# SprinklerController.net
KiCad netlist of a schematic drawn in EAGLE
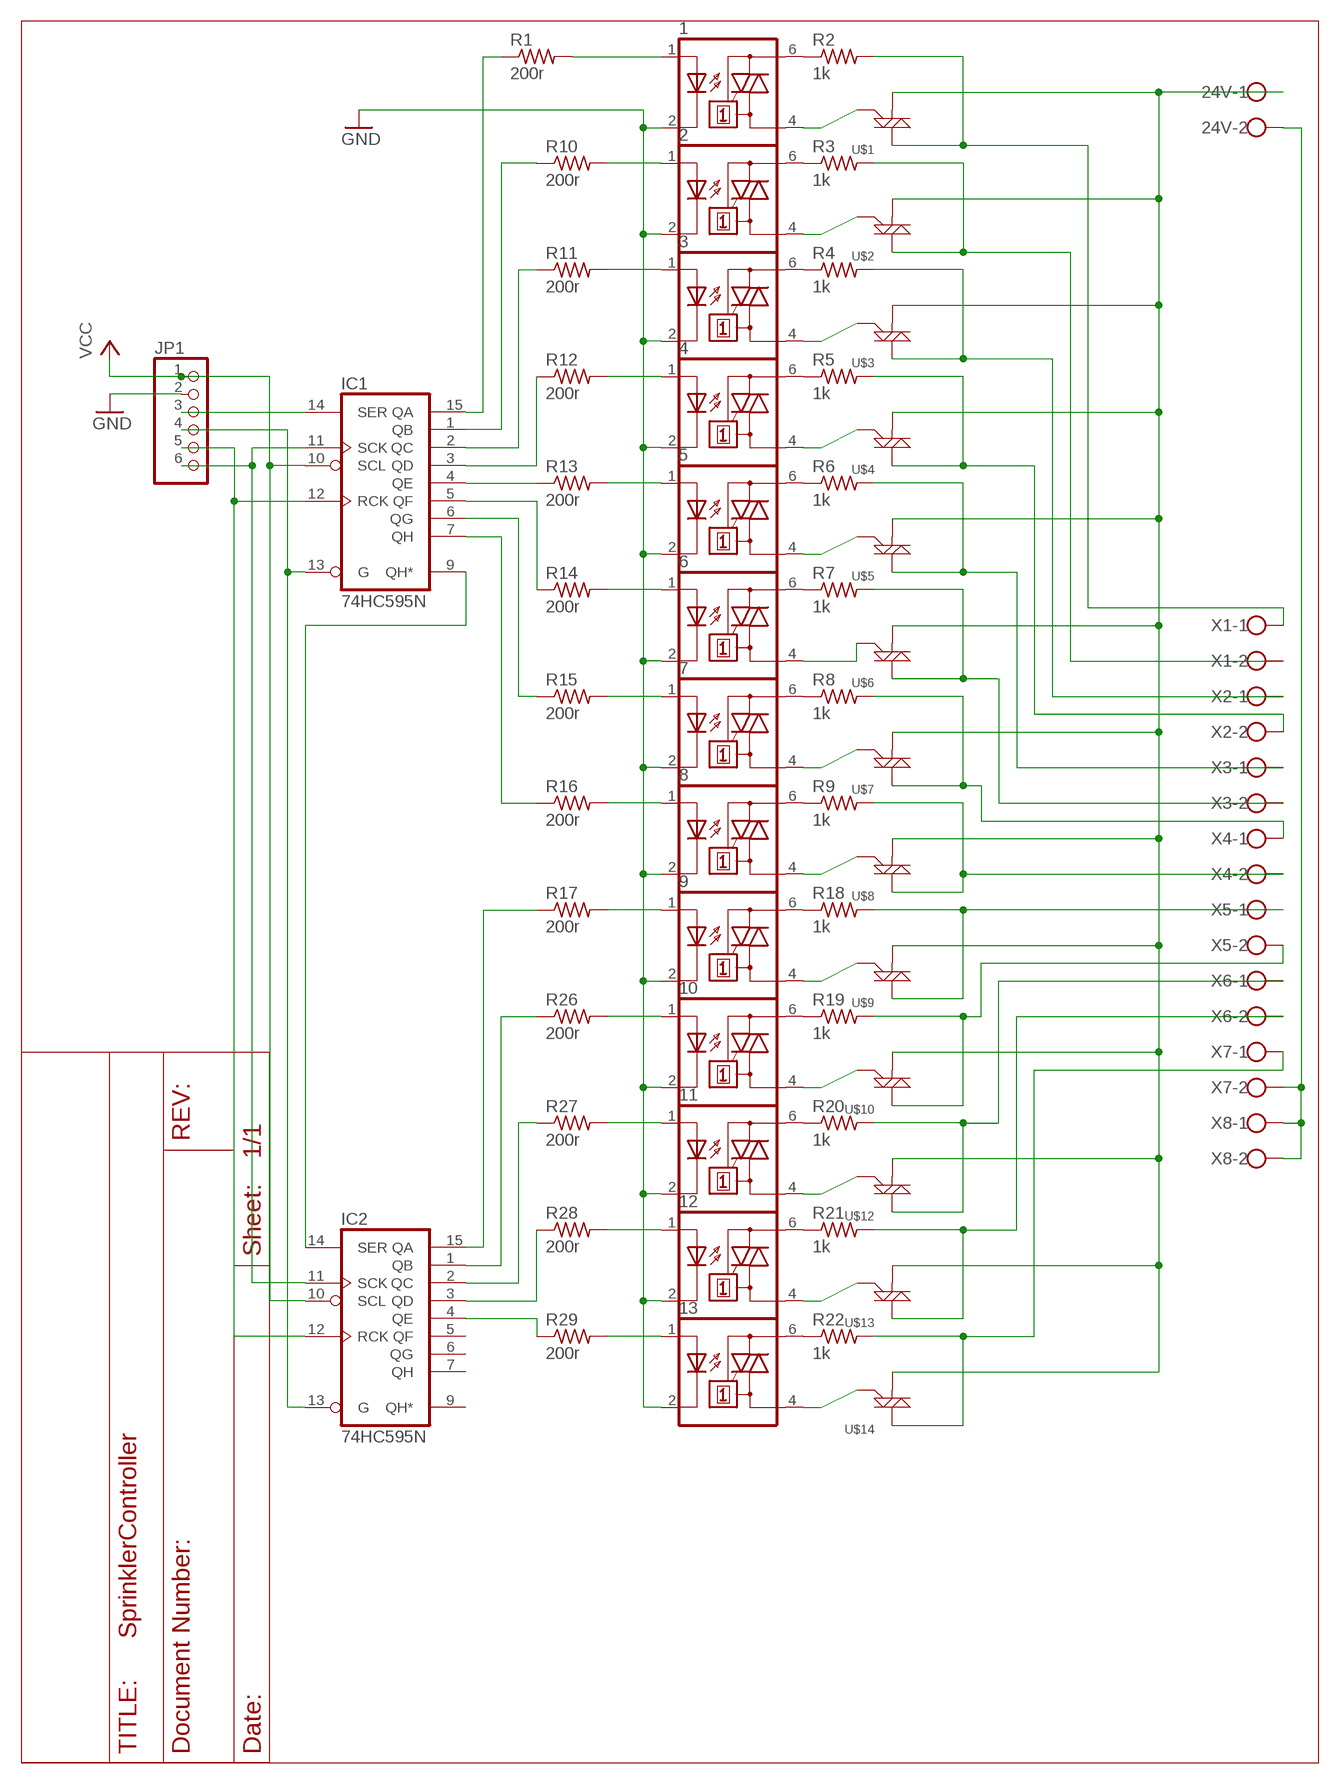
[diagram p0: schematic, sheet 1]

(export (version "E")
  (design (tool "Eeschema 10.0.6"))
  (components
    (comp (ref "1")
      (value "MOC3021M")
      (footprint "eagle-import:DIL06")
      (fields (field (name "MF") "FAIRCHILD SEMICONDUCTOR") (field (name "MPN") "MOC3021-M"))
      (libsource (lib "eagle-import") (part "MOC30M21"))
    )
    (comp (ref "2")
      (value "MOC3021M")
      (footprint "eagle-import:DIL06")
      (fields (field (name "MF") "FAIRCHILD SEMICONDUCTOR") (field (name "MPN") "MOC3021-M"))
      (libsource (lib "eagle-import") (part "MOC30M21"))
    )
    (comp (ref "3")
      (value "MOC3021M")
      (footprint "eagle-import:DIL06")
      (fields (field (name "MF") "FAIRCHILD SEMICONDUCTOR") (field (name "MPN") "MOC3021-M"))
      (libsource (lib "eagle-import") (part "MOC30M21"))
    )
    (comp (ref "4")
      (value "MOC3021M")
      (footprint "eagle-import:DIL06")
      (fields (field (name "MF") "FAIRCHILD SEMICONDUCTOR") (field (name "MPN") "MOC3021-M"))
      (libsource (lib "eagle-import") (part "MOC30M21"))
    )
    (comp (ref "5")
      (value "MOC3021M")
      (footprint "eagle-import:DIL06")
      (fields (field (name "MF") "FAIRCHILD SEMICONDUCTOR") (field (name "MPN") "MOC3021-M"))
      (libsource (lib "eagle-import") (part "MOC30M21"))
    )
    (comp (ref "6")
      (value "MOC3021M")
      (footprint "eagle-import:DIL06")
      (fields (field (name "MF") "FAIRCHILD SEMICONDUCTOR") (field (name "MPN") "MOC3021-M"))
      (libsource (lib "eagle-import") (part "MOC30M21"))
    )
    (comp (ref "7")
      (value "MOC3021M")
      (footprint "eagle-import:DIL06")
      (fields (field (name "MF") "FAIRCHILD SEMICONDUCTOR") (field (name "MPN") "MOC3021-M"))
      (libsource (lib "eagle-import") (part "MOC30M21"))
    )
    (comp (ref "8")
      (value "MOC3021M")
      (footprint "eagle-import:DIL06")
      (fields (field (name "MF") "FAIRCHILD SEMICONDUCTOR") (field (name "MPN") "MOC3021-M"))
      (libsource (lib "eagle-import") (part "MOC30M21"))
    )
    (comp (ref "9")
      (value "MOC3021M")
      (footprint "eagle-import:DIL06")
      (fields (field (name "MF") "FAIRCHILD SEMICONDUCTOR") (field (name "MPN") "MOC3021-M"))
      (libsource (lib "eagle-import") (part "MOC30M21"))
    )
    (comp (ref "10")
      (value "MOC3021M")
      (footprint "eagle-import:DIL06")
      (fields (field (name "MF") "FAIRCHILD SEMICONDUCTOR") (field (name "MPN") "MOC3021-M"))
      (libsource (lib "eagle-import") (part "MOC30M21"))
    )
    (comp (ref "11")
      (value "MOC3021M")
      (footprint "eagle-import:DIL06")
      (fields (field (name "MF") "FAIRCHILD SEMICONDUCTOR") (field (name "MPN") "MOC3021-M"))
      (libsource (lib "eagle-import") (part "MOC30M21"))
    )
    (comp (ref "12")
      (value "MOC3021M")
      (footprint "eagle-import:DIL06")
      (fields (field (name "MF") "FAIRCHILD SEMICONDUCTOR") (field (name "MPN") "MOC3021-M"))
      (libsource (lib "eagle-import") (part "MOC30M21"))
    )
    (comp (ref "13")
      (value "MOC3021M")
      (footprint "eagle-import:DIL06")
      (fields (field (name "MF") "FAIRCHILD SEMICONDUCTOR") (field (name "MPN") "MOC3021-M"))
      (libsource (lib "eagle-import") (part "MOC30M21"))
    )
    (comp (ref "24V")
      (value "W237-102")
      (footprint "eagle-import:W237-102")
      (fields (field (name "MPN") "237-102"))
      (libsource (lib "eagle-import") (part "W237-102"))
    )
    (comp (ref "IC1")
      (value "74HC595N")
      (footprint "eagle-import:DIL16")
      (libsource (lib "eagle-import") (part "74595NLS"))
    )
    (comp (ref "IC2")
      (value "74HC595N")
      (footprint "eagle-import:DIL16")
      (libsource (lib "eagle-import") (part "74595NLS"))
    )
    (comp (ref "JP1")
      (value "PINHD-1X6")
      (footprint "eagle-import:1X06")
      (libsource (lib "eagle-import") (part "PINHD-1X6"))
    )
    (comp (ref "R1")
      (value "200r")
      (footprint "eagle-import:0204_7")
      (libsource (lib "eagle-import") (part "R-US_0204/7"))
    )
    (comp (ref "R2")
      (value "1k")
      (footprint "eagle-import:0204_7")
      (libsource (lib "eagle-import") (part "R-US_0204/7"))
    )
    (comp (ref "R3")
      (value "1k")
      (footprint "eagle-import:0204_7")
      (libsource (lib "eagle-import") (part "R-US_0204/7"))
    )
    (comp (ref "R4")
      (value "1k")
      (footprint "eagle-import:0204_7")
      (libsource (lib "eagle-import") (part "R-US_0204/7"))
    )
    (comp (ref "R5")
      (value "1k")
      (footprint "eagle-import:0204_7")
      (libsource (lib "eagle-import") (part "R-US_0204/7"))
    )
    (comp (ref "R6")
      (value "1k")
      (footprint "eagle-import:0204_7")
      (libsource (lib "eagle-import") (part "R-US_0204/7"))
    )
    (comp (ref "R7")
      (value "1k")
      (footprint "eagle-import:0204_7")
      (libsource (lib "eagle-import") (part "R-US_0204/7"))
    )
    (comp (ref "R8")
      (value "1k")
      (footprint "eagle-import:0204_7")
      (libsource (lib "eagle-import") (part "R-US_0204/7"))
    )
    (comp (ref "R9")
      (value "1k")
      (footprint "eagle-import:0204_7")
      (libsource (lib "eagle-import") (part "R-US_0204/7"))
    )
    (comp (ref "R10")
      (value "200r")
      (footprint "eagle-import:0204_7")
      (libsource (lib "eagle-import") (part "R-US_0204/7"))
    )
    (comp (ref "R11")
      (value "200r")
      (footprint "eagle-import:0204_7")
      (libsource (lib "eagle-import") (part "R-US_0204/7"))
    )
    (comp (ref "R12")
      (value "200r")
      (footprint "eagle-import:0204_7")
      (libsource (lib "eagle-import") (part "R-US_0204/7"))
    )
    (comp (ref "R13")
      (value "200r")
      (footprint "eagle-import:0204_7")
      (libsource (lib "eagle-import") (part "R-US_0204/7"))
    )
    (comp (ref "R14")
      (value "200r")
      (footprint "eagle-import:0204_7")
      (libsource (lib "eagle-import") (part "R-US_0204/7"))
    )
    (comp (ref "R15")
      (value "200r")
      (footprint "eagle-import:0204_7")
      (libsource (lib "eagle-import") (part "R-US_0204/7"))
    )
    (comp (ref "R16")
      (value "200r")
      (footprint "eagle-import:0204_7")
      (libsource (lib "eagle-import") (part "R-US_0204/7"))
    )
    (comp (ref "R17")
      (value "200r")
      (footprint "eagle-import:0204_7")
      (libsource (lib "eagle-import") (part "R-US_0204/7"))
    )
    (comp (ref "R18")
      (value "1k")
      (footprint "eagle-import:0204_7")
      (libsource (lib "eagle-import") (part "R-US_0204/7"))
    )
    (comp (ref "R19")
      (value "1k")
      (footprint "eagle-import:0204_7")
      (libsource (lib "eagle-import") (part "R-US_0204/7"))
    )
    (comp (ref "R20")
      (value "1k")
      (footprint "eagle-import:0204_7")
      (libsource (lib "eagle-import") (part "R-US_0204/7"))
    )
    (comp (ref "R21")
      (value "1k")
      (footprint "eagle-import:0204_7")
      (libsource (lib "eagle-import") (part "R-US_0204/7"))
    )
    (comp (ref "R22")
      (value "1k")
      (footprint "eagle-import:0204_7")
      (libsource (lib "eagle-import") (part "R-US_0204/7"))
    )
    (comp (ref "R26")
      (value "200r")
      (footprint "eagle-import:0204_7")
      (libsource (lib "eagle-import") (part "R-US_0204/7"))
    )
    (comp (ref "R27")
      (value "200r")
      (footprint "eagle-import:0204_7")
      (libsource (lib "eagle-import") (part "R-US_0204/7"))
    )
    (comp (ref "R28")
      (value "200r")
      (footprint "eagle-import:0204_7")
      (libsource (lib "eagle-import") (part "R-US_0204/7"))
    )
    (comp (ref "R29")
      (value "200r")
      (footprint "eagle-import:0204_7")
      (libsource (lib "eagle-import") (part "R-US_0204/7"))
    )
    (comp (ref "U$1")
      (value "TRIACPTH")
      (footprint "eagle-import:TO-92")
      (libsource (lib "eagle-import") (part "TRIACPTH"))
    )
    (comp (ref "U$2")
      (value "TRIACPTH")
      (footprint "eagle-import:TO-92")
      (libsource (lib "eagle-import") (part "TRIACPTH"))
    )
    (comp (ref "U$3")
      (value "TRIACPTH")
      (footprint "eagle-import:TO-92")
      (libsource (lib "eagle-import") (part "TRIACPTH"))
    )
    (comp (ref "U$4")
      (value "TRIACPTH")
      (footprint "eagle-import:TO-92")
      (libsource (lib "eagle-import") (part "TRIACPTH"))
    )
    (comp (ref "U$5")
      (value "TRIACPTH")
      (footprint "eagle-import:TO-92")
      (libsource (lib "eagle-import") (part "TRIACPTH"))
    )
    (comp (ref "U$6")
      (value "TRIACPTH")
      (footprint "eagle-import:TO-92")
      (libsource (lib "eagle-import") (part "TRIACPTH"))
    )
    (comp (ref "U$7")
      (value "TRIACPTH")
      (footprint "eagle-import:TO-92")
      (libsource (lib "eagle-import") (part "TRIACPTH"))
    )
    (comp (ref "U$8")
      (value "TRIACPTH")
      (footprint "eagle-import:TO-92")
      (libsource (lib "eagle-import") (part "TRIACPTH"))
    )
    (comp (ref "U$9")
      (value "TRIACPTH")
      (footprint "eagle-import:TO-92")
      (libsource (lib "eagle-import") (part "TRIACPTH"))
    )
    (comp (ref "U$10")
      (value "TRIACPTH")
      (footprint "eagle-import:TO-92")
      (libsource (lib "eagle-import") (part "TRIACPTH"))
    )
    (comp (ref "U$12")
      (value "TRIACPTH")
      (footprint "eagle-import:TO-92")
      (libsource (lib "eagle-import") (part "TRIACPTH"))
    )
    (comp (ref "U$13")
      (value "TRIACPTH")
      (footprint "eagle-import:TO-92")
      (libsource (lib "eagle-import") (part "TRIACPTH"))
    )
    (comp (ref "U$14")
      (value "TRIACPTH")
      (footprint "eagle-import:TO-92")
      (libsource (lib "eagle-import") (part "TRIACPTH"))
    )
    (comp (ref "X1")
      (value "W237-102")
      (footprint "eagle-import:W237-102")
      (fields (field (name "MPN") "237-102"))
      (libsource (lib "eagle-import") (part "W237-102"))
    )
    (comp (ref "X2")
      (value "W237-102")
      (footprint "eagle-import:W237-102")
      (fields (field (name "MPN") "237-102"))
      (libsource (lib "eagle-import") (part "W237-102"))
    )
    (comp (ref "X3")
      (value "W237-102")
      (footprint "eagle-import:W237-102")
      (fields (field (name "MPN") "237-102"))
      (libsource (lib "eagle-import") (part "W237-102"))
    )
    (comp (ref "X4")
      (value "W237-102")
      (footprint "eagle-import:W237-102")
      (fields (field (name "MPN") "237-102"))
      (libsource (lib "eagle-import") (part "W237-102"))
    )
    (comp (ref "X5")
      (value "W237-102")
      (footprint "eagle-import:W237-102")
      (fields (field (name "MPN") "237-102"))
      (libsource (lib "eagle-import") (part "W237-102"))
    )
    (comp (ref "X6")
      (value "W237-102")
      (footprint "eagle-import:W237-102")
      (fields (field (name "MPN") "237-102"))
      (libsource (lib "eagle-import") (part "W237-102"))
    )
    (comp (ref "X7")
      (value "W237-102")
      (footprint "eagle-import:W237-102")
      (fields (field (name "MPN") "237-102"))
      (libsource (lib "eagle-import") (part "W237-102"))
    )
    (comp (ref "X8")
      (value "W237-102")
      (footprint "eagle-import:W237-102")
      (fields (field (name "MPN") "237-102"))
      (libsource (lib "eagle-import") (part "W237-102"))
    )
  )
  (nets
    (net (code "1") (name "GND") (class "Default")
      (node (ref "1") (pin "2") (pinfunction "C_2") (pintype "passive"))
      (node (ref "10") (pin "2") (pinfunction "C_2") (pintype "passive"))
      (node (ref "11") (pin "2") (pinfunction "C_2") (pintype "passive"))
      (node (ref "12") (pin "2") (pinfunction "C_2") (pintype "passive"))
      (node (ref "13") (pin "2") (pinfunction "C_2") (pintype "passive"))
      (node (ref "2") (pin "2") (pinfunction "C_2") (pintype "passive"))
      (node (ref "3") (pin "2") (pinfunction "C_2") (pintype "passive"))
      (node (ref "4") (pin "2") (pinfunction "C_2") (pintype "passive"))
      (node (ref "5") (pin "2") (pinfunction "C_2") (pintype "passive"))
      (node (ref "6") (pin "2") (pinfunction "C_2") (pintype "passive"))
      (node (ref "7") (pin "2") (pinfunction "C_2") (pintype "passive"))
      (node (ref "8") (pin "2") (pinfunction "C_2") (pintype "passive"))
      (node (ref "9") (pin "2") (pinfunction "C_2") (pintype "passive"))
      (node (ref "JP1") (pin "2") (pinfunction "2_2") (pintype "passive"))
    )
    (net (code "2") (name "Net-(1-A)") (class "Default")
      (node (ref "1") (pin "1") (pinfunction "A_1") (pintype "passive"))
      (node (ref "R1") (pin "2") (pinfunction "2_2") (pintype "passive"))
    )
    (net (code "3") (name "Net-(1-A1)") (class "Default")
      (node (ref "1") (pin "4") (pinfunction "A1_4") (pintype "passive"))
      (node (ref "U$1") (pin "2") (pinfunction "G_2") (pintype "bidirectional"))
    )
    (net (code "4") (name "Net-(1-A2)") (class "Default")
      (node (ref "1") (pin "6") (pinfunction "A2_6") (pintype "passive"))
      (node (ref "R2") (pin "1") (pinfunction "1_1") (pintype "passive"))
    )
    (net (code "5") (name "Net-(2-A)") (class "Default")
      (node (ref "2") (pin "1") (pinfunction "A_1") (pintype "passive"))
      (node (ref "R10") (pin "2") (pinfunction "2_2") (pintype "passive"))
    )
    (net (code "6") (name "Net-(2-A1)") (class "Default")
      (node (ref "2") (pin "4") (pinfunction "A1_4") (pintype "passive"))
      (node (ref "U$2") (pin "2") (pinfunction "G_2") (pintype "bidirectional"))
    )
    (net (code "7") (name "Net-(2-A2)") (class "Default")
      (node (ref "2") (pin "6") (pinfunction "A2_6") (pintype "passive"))
      (node (ref "R3") (pin "1") (pinfunction "1_1") (pintype "passive"))
    )
    (net (code "8") (name "Net-(3-A)") (class "Default")
      (node (ref "3") (pin "1") (pinfunction "A_1") (pintype "passive"))
      (node (ref "R11") (pin "2") (pinfunction "2_2") (pintype "passive"))
    )
    (net (code "9") (name "Net-(3-A1)") (class "Default")
      (node (ref "3") (pin "4") (pinfunction "A1_4") (pintype "passive"))
      (node (ref "U$3") (pin "2") (pinfunction "G_2") (pintype "bidirectional"))
    )
    (net (code "10") (name "Net-(3-A2)") (class "Default")
      (node (ref "3") (pin "6") (pinfunction "A2_6") (pintype "passive"))
      (node (ref "R4") (pin "1") (pinfunction "1_1") (pintype "passive"))
    )
    (net (code "11") (name "Net-(4-A)") (class "Default")
      (node (ref "4") (pin "1") (pinfunction "A_1") (pintype "passive"))
      (node (ref "R12") (pin "2") (pinfunction "2_2") (pintype "passive"))
    )
    (net (code "12") (name "Net-(4-A1)") (class "Default")
      (node (ref "4") (pin "4") (pinfunction "A1_4") (pintype "passive"))
      (node (ref "U$4") (pin "2") (pinfunction "G_2") (pintype "bidirectional"))
    )
    (net (code "13") (name "Net-(4-A2)") (class "Default")
      (node (ref "4") (pin "6") (pinfunction "A2_6") (pintype "passive"))
      (node (ref "R5") (pin "1") (pinfunction "1_1") (pintype "passive"))
    )
    (net (code "14") (name "Net-(5-A)") (class "Default")
      (node (ref "5") (pin "1") (pinfunction "A_1") (pintype "passive"))
      (node (ref "R13") (pin "2") (pinfunction "2_2") (pintype "passive"))
    )
    (net (code "15") (name "Net-(5-A1)") (class "Default")
      (node (ref "5") (pin "4") (pinfunction "A1_4") (pintype "passive"))
      (node (ref "U$5") (pin "2") (pinfunction "G_2") (pintype "bidirectional"))
    )
    (net (code "16") (name "Net-(5-A2)") (class "Default")
      (node (ref "5") (pin "6") (pinfunction "A2_6") (pintype "passive"))
      (node (ref "R6") (pin "1") (pinfunction "1_1") (pintype "passive"))
    )
    (net (code "17") (name "Net-(6-A)") (class "Default")
      (node (ref "6") (pin "1") (pinfunction "A_1") (pintype "passive"))
      (node (ref "R14") (pin "2") (pinfunction "2_2") (pintype "passive"))
    )
    (net (code "18") (name "Net-(6-A1)") (class "Default")
      (node (ref "6") (pin "4") (pinfunction "A1_4") (pintype "passive"))
      (node (ref "U$6") (pin "2") (pinfunction "G_2") (pintype "bidirectional"))
    )
    (net (code "19") (name "Net-(6-A2)") (class "Default")
      (node (ref "6") (pin "6") (pinfunction "A2_6") (pintype "passive"))
      (node (ref "R7") (pin "1") (pinfunction "1_1") (pintype "passive"))
    )
    (net (code "20") (name "Net-(7-A)") (class "Default")
      (node (ref "7") (pin "1") (pinfunction "A_1") (pintype "passive"))
      (node (ref "R15") (pin "2") (pinfunction "2_2") (pintype "passive"))
    )
    (net (code "21") (name "Net-(7-A1)") (class "Default")
      (node (ref "7") (pin "4") (pinfunction "A1_4") (pintype "passive"))
      (node (ref "U$7") (pin "2") (pinfunction "G_2") (pintype "bidirectional"))
    )
    (net (code "22") (name "Net-(7-A2)") (class "Default")
      (node (ref "7") (pin "6") (pinfunction "A2_6") (pintype "passive"))
      (node (ref "R8") (pin "1") (pinfunction "1_1") (pintype "passive"))
    )
    (net (code "23") (name "Net-(8-A)") (class "Default")
      (node (ref "8") (pin "1") (pinfunction "A_1") (pintype "passive"))
      (node (ref "R16") (pin "2") (pinfunction "2_2") (pintype "passive"))
    )
    (net (code "24") (name "Net-(8-A1)") (class "Default")
      (node (ref "8") (pin "4") (pinfunction "A1_4") (pintype "passive"))
      (node (ref "U$8") (pin "2") (pinfunction "G_2") (pintype "bidirectional"))
    )
    (net (code "25") (name "Net-(8-A2)") (class "Default")
      (node (ref "8") (pin "6") (pinfunction "A2_6") (pintype "passive"))
      (node (ref "R9") (pin "1") (pinfunction "1_1") (pintype "passive"))
    )
    (net (code "26") (name "Net-(9-A)") (class "Default")
      (node (ref "9") (pin "1") (pinfunction "A_1") (pintype "passive"))
      (node (ref "R17") (pin "2") (pinfunction "2_2") (pintype "passive"))
    )
    (net (code "27") (name "Net-(9-A1)") (class "Default")
      (node (ref "9") (pin "4") (pinfunction "A1_4") (pintype "passive"))
      (node (ref "U$9") (pin "2") (pinfunction "G_2") (pintype "bidirectional"))
    )
    (net (code "28") (name "Net-(9-A2)") (class "Default")
      (node (ref "9") (pin "6") (pinfunction "A2_6") (pintype "passive"))
      (node (ref "R18") (pin "1") (pinfunction "1_1") (pintype "passive"))
    )
    (net (code "29") (name "Net-(10-A)") (class "Default")
      (node (ref "10") (pin "1") (pinfunction "A_1") (pintype "passive"))
      (node (ref "R26") (pin "2") (pinfunction "2_2") (pintype "passive"))
    )
    (net (code "30") (name "Net-(10-A1)") (class "Default")
      (node (ref "10") (pin "4") (pinfunction "A1_4") (pintype "passive"))
      (node (ref "U$10") (pin "2") (pinfunction "G_2") (pintype "bidirectional"))
    )
    (net (code "31") (name "Net-(10-A2)") (class "Default")
      (node (ref "10") (pin "6") (pinfunction "A2_6") (pintype "passive"))
      (node (ref "R19") (pin "1") (pinfunction "1_1") (pintype "passive"))
    )
    (net (code "32") (name "Net-(11-A)") (class "Default")
      (node (ref "11") (pin "1") (pinfunction "A_1") (pintype "passive"))
      (node (ref "R27") (pin "2") (pinfunction "2_2") (pintype "passive"))
    )
    (net (code "33") (name "Net-(11-A1)") (class "Default")
      (node (ref "11") (pin "4") (pinfunction "A1_4") (pintype "passive"))
      (node (ref "U$12") (pin "2") (pinfunction "G_2") (pintype "bidirectional"))
    )
    (net (code "34") (name "Net-(11-A2)") (class "Default")
      (node (ref "11") (pin "6") (pinfunction "A2_6") (pintype "passive"))
      (node (ref "R20") (pin "1") (pinfunction "1_1") (pintype "passive"))
    )
    (net (code "35") (name "Net-(12-A)") (class "Default")
      (node (ref "12") (pin "1") (pinfunction "A_1") (pintype "passive"))
      (node (ref "R28") (pin "2") (pinfunction "2_2") (pintype "passive"))
    )
    (net (code "36") (name "Net-(12-A1)") (class "Default")
      (node (ref "12") (pin "4") (pinfunction "A1_4") (pintype "passive"))
      (node (ref "U$13") (pin "2") (pinfunction "G_2") (pintype "bidirectional"))
    )
    (net (code "37") (name "Net-(12-A2)") (class "Default")
      (node (ref "12") (pin "6") (pinfunction "A2_6") (pintype "passive"))
      (node (ref "R21") (pin "1") (pinfunction "1_1") (pintype "passive"))
    )
    (net (code "38") (name "Net-(13-A)") (class "Default")
      (node (ref "13") (pin "1") (pinfunction "A_1") (pintype "passive"))
      (node (ref "R29") (pin "2") (pinfunction "2_2") (pintype "passive"))
    )
    (net (code "39") (name "Net-(13-A1)") (class "Default")
      (node (ref "13") (pin "4") (pinfunction "A1_4") (pintype "passive"))
      (node (ref "U$14") (pin "2") (pinfunction "G_2") (pintype "bidirectional"))
    )
    (net (code "40") (name "Net-(13-A2)") (class "Default")
      (node (ref "13") (pin "6") (pinfunction "A2_6") (pintype "passive"))
      (node (ref "R22") (pin "1") (pinfunction "1_1") (pintype "passive"))
    )
    (net (code "41") (name "Net-(24VA-KL)") (class "Default")
      (node (ref "24V") (pin "1") (pinfunction "KL_1") (pintype "passive"))
      (node (ref "U$1") (pin "1") (pinfunction "M1_1") (pintype "bidirectional"))
      (node (ref "U$10") (pin "1") (pinfunction "M1_1") (pintype "bidirectional"))
      (node (ref "U$12") (pin "1") (pinfunction "M1_1") (pintype "bidirectional"))
      (node (ref "U$13") (pin "1") (pinfunction "M1_1") (pintype "bidirectional"))
      (node (ref "U$14") (pin "1") (pinfunction "M1_1") (pintype "bidirectional"))
      (node (ref "U$2") (pin "1") (pinfunction "M1_1") (pintype "bidirectional"))
      (node (ref "U$3") (pin "1") (pinfunction "M1_1") (pintype "bidirectional"))
      (node (ref "U$4") (pin "1") (pinfunction "M1_1") (pintype "bidirectional"))
      (node (ref "U$5") (pin "1") (pinfunction "M1_1") (pintype "bidirectional"))
      (node (ref "U$6") (pin "1") (pinfunction "M1_1") (pintype "bidirectional"))
      (node (ref "U$7") (pin "1") (pinfunction "M1_1") (pintype "bidirectional"))
      (node (ref "U$8") (pin "1") (pinfunction "M1_1") (pintype "bidirectional"))
      (node (ref "U$9") (pin "1") (pinfunction "M1_1") (pintype "bidirectional"))
    )
    (net (code "42") (name "Net-(24VB-KL)") (class "Default")
      (node (ref "24V") (pin "2") (pinfunction "KL_2") (pintype "passive"))
      (node (ref "X7") (pin "2") (pinfunction "KL_2") (pintype "passive"))
      (node (ref "X8") (pin "1") (pinfunction "KL_1") (pintype "passive"))
      (node (ref "X8") (pin "2") (pinfunction "KL_2") (pintype "passive"))
    )
    (net (code "43") (name "Net-(IC1A-G)") (class "Default")
      (node (ref "IC1") (pin "13") (pinfunction "G_13") (pintype "input"))
      (node (ref "IC2") (pin "13") (pinfunction "G_13") (pintype "input"))
      (node (ref "JP1") (pin "4") (pinfunction "4_4") (pintype "passive"))
    )
    (net (code "44") (name "Net-(IC1A-QA)") (class "Default")
      (node (ref "IC1") (pin "15") (pinfunction "QA_15") (pintype "tri_state"))
      (node (ref "R1") (pin "1") (pinfunction "1_1") (pintype "passive"))
    )
    (net (code "45") (name "Net-(IC1A-QB)") (class "Default")
      (node (ref "IC1") (pin "1") (pinfunction "QB_1") (pintype "tri_state"))
      (node (ref "R10") (pin "1") (pinfunction "1_1") (pintype "passive"))
    )
    (net (code "46") (name "Net-(IC1A-QC)") (class "Default")
      (node (ref "IC1") (pin "2") (pinfunction "QC_2") (pintype "tri_state"))
      (node (ref "R11") (pin "1") (pinfunction "1_1") (pintype "passive"))
    )
    (net (code "47") (name "Net-(IC1A-QD)") (class "Default")
      (node (ref "IC1") (pin "3") (pinfunction "QD_3") (pintype "tri_state"))
      (node (ref "R12") (pin "1") (pinfunction "1_1") (pintype "passive"))
    )
    (net (code "48") (name "Net-(IC1A-QE)") (class "Default")
      (node (ref "IC1") (pin "4") (pinfunction "QE_4") (pintype "tri_state"))
      (node (ref "R13") (pin "1") (pinfunction "1_1") (pintype "passive"))
    )
    (net (code "49") (name "Net-(IC1A-QF)") (class "Default")
      (node (ref "IC1") (pin "5") (pinfunction "QF_5") (pintype "tri_state"))
      (node (ref "R14") (pin "1") (pinfunction "1_1") (pintype "passive"))
    )
    (net (code "50") (name "Net-(IC1A-QG)") (class "Default")
      (node (ref "IC1") (pin "6") (pinfunction "QG_6") (pintype "tri_state"))
      (node (ref "R15") (pin "1") (pinfunction "1_1") (pintype "passive"))
    )
    (net (code "51") (name "Net-(IC1A-QH)") (class "Default")
      (node (ref "IC1") (pin "7") (pinfunction "QH_7") (pintype "tri_state"))
      (node (ref "R16") (pin "1") (pinfunction "1_1") (pintype "passive"))
    )
    (net (code "52") (name "Net-(IC1A-QH*)") (class "Default")
      (node (ref "IC1") (pin "9") (pinfunction "QH*_9") (pintype "tri_state"))
      (node (ref "IC2") (pin "14") (pinfunction "SER_14") (pintype "input"))
    )
    (net (code "53") (name "Net-(IC1A-RCK)") (class "Default")
      (node (ref "IC1") (pin "12") (pinfunction "RCK_12") (pintype "input"))
      (node (ref "IC2") (pin "12") (pinfunction "RCK_12") (pintype "input"))
      (node (ref "JP1") (pin "5") (pinfunction "5_5") (pintype "passive"))
    )
    (net (code "54") (name "Net-(IC1A-SCK)") (class "Default")
      (node (ref "IC1") (pin "11") (pinfunction "SCK_11") (pintype "input"))
      (node (ref "IC2") (pin "11") (pinfunction "SCK_11") (pintype "input"))
      (node (ref "JP1") (pin "6") (pinfunction "6_6") (pintype "passive"))
    )
    (net (code "55") (name "Net-(IC1A-SER)") (class "Default")
      (node (ref "IC1") (pin "14") (pinfunction "SER_14") (pintype "input"))
      (node (ref "JP1") (pin "3") (pinfunction "3_3") (pintype "passive"))
    )
    (net (code "56") (name "Net-(IC2A-QA)") (class "Default")
      (node (ref "IC2") (pin "15") (pinfunction "QA_15") (pintype "tri_state"))
      (node (ref "R17") (pin "1") (pinfunction "1_1") (pintype "passive"))
    )
    (net (code "57") (name "Net-(IC2A-QB)") (class "Default")
      (node (ref "IC2") (pin "1") (pinfunction "QB_1") (pintype "tri_state"))
      (node (ref "R26") (pin "1") (pinfunction "1_1") (pintype "passive"))
    )
    (net (code "58") (name "Net-(IC2A-QC)") (class "Default")
      (node (ref "IC2") (pin "2") (pinfunction "QC_2") (pintype "tri_state"))
      (node (ref "R27") (pin "1") (pinfunction "1_1") (pintype "passive"))
    )
    (net (code "59") (name "Net-(IC2A-QD)") (class "Default")
      (node (ref "IC2") (pin "3") (pinfunction "QD_3") (pintype "tri_state"))
      (node (ref "R28") (pin "1") (pinfunction "1_1") (pintype "passive"))
    )
    (net (code "60") (name "Net-(IC2A-QE)") (class "Default")
      (node (ref "IC2") (pin "4") (pinfunction "QE_4") (pintype "tri_state"))
      (node (ref "R29") (pin "1") (pinfunction "1_1") (pintype "passive"))
    )
    (net (code "61") (name "Net-(U$1-M2)") (class "Default")
      (node (ref "R2") (pin "2") (pinfunction "2_2") (pintype "passive"))
      (node (ref "U$1") (pin "3") (pinfunction "M2_3") (pintype "bidirectional"))
      (node (ref "X1") (pin "1") (pinfunction "KL_1") (pintype "passive"))
    )
    (net (code "62") (name "Net-(U$2-M2)") (class "Default")
      (node (ref "R3") (pin "2") (pinfunction "2_2") (pintype "passive"))
      (node (ref "U$2") (pin "3") (pinfunction "M2_3") (pintype "bidirectional"))
      (node (ref "X1") (pin "2") (pinfunction "KL_2") (pintype "passive"))
    )
    (net (code "63") (name "Net-(U$3-M2)") (class "Default")
      (node (ref "R4") (pin "2") (pinfunction "2_2") (pintype "passive"))
      (node (ref "U$3") (pin "3") (pinfunction "M2_3") (pintype "bidirectional"))
      (node (ref "X2") (pin "1") (pinfunction "KL_1") (pintype "passive"))
    )
    (net (code "64") (name "Net-(U$4-M2)") (class "Default")
      (node (ref "R5") (pin "2") (pinfunction "2_2") (pintype "passive"))
      (node (ref "U$4") (pin "3") (pinfunction "M2_3") (pintype "bidirectional"))
      (node (ref "X2") (pin "2") (pinfunction "KL_2") (pintype "passive"))
    )
    (net (code "65") (name "Net-(U$5-M2)") (class "Default")
      (node (ref "R6") (pin "2") (pinfunction "2_2") (pintype "passive"))
      (node (ref "U$5") (pin "3") (pinfunction "M2_3") (pintype "bidirectional"))
      (node (ref "X3") (pin "1") (pinfunction "KL_1") (pintype "passive"))
    )
    (net (code "66") (name "Net-(U$6-M2)") (class "Default")
      (node (ref "R7") (pin "2") (pinfunction "2_2") (pintype "passive"))
      (node (ref "U$6") (pin "3") (pinfunction "M2_3") (pintype "bidirectional"))
      (node (ref "X3") (pin "2") (pinfunction "KL_2") (pintype "passive"))
    )
    (net (code "67") (name "Net-(U$7-M2)") (class "Default")
      (node (ref "R8") (pin "2") (pinfunction "2_2") (pintype "passive"))
      (node (ref "U$7") (pin "3") (pinfunction "M2_3") (pintype "bidirectional"))
      (node (ref "X4") (pin "1") (pinfunction "KL_1") (pintype "passive"))
    )
    (net (code "68") (name "Net-(U$8-M2)") (class "Default")
      (node (ref "R9") (pin "2") (pinfunction "2_2") (pintype "passive"))
      (node (ref "U$8") (pin "3") (pinfunction "M2_3") (pintype "bidirectional"))
      (node (ref "X4") (pin "2") (pinfunction "KL_2") (pintype "passive"))
    )
    (net (code "69") (name "Net-(U$9-M2)") (class "Default")
      (node (ref "R18") (pin "2") (pinfunction "2_2") (pintype "passive"))
      (node (ref "U$9") (pin "3") (pinfunction "M2_3") (pintype "bidirectional"))
      (node (ref "X5") (pin "1") (pinfunction "KL_1") (pintype "passive"))
    )
    (net (code "70") (name "Net-(U$10-M2)") (class "Default")
      (node (ref "R19") (pin "2") (pinfunction "2_2") (pintype "passive"))
      (node (ref "U$10") (pin "3") (pinfunction "M2_3") (pintype "bidirectional"))
      (node (ref "X5") (pin "2") (pinfunction "KL_2") (pintype "passive"))
    )
    (net (code "71") (name "Net-(U$12-M2)") (class "Default")
      (node (ref "R20") (pin "2") (pinfunction "2_2") (pintype "passive"))
      (node (ref "U$12") (pin "3") (pinfunction "M2_3") (pintype "bidirectional"))
      (node (ref "X6") (pin "1") (pinfunction "KL_1") (pintype "passive"))
    )
    (net (code "72") (name "Net-(U$13-M2)") (class "Default")
      (node (ref "R21") (pin "2") (pinfunction "2_2") (pintype "passive"))
      (node (ref "U$13") (pin "3") (pinfunction "M2_3") (pintype "bidirectional"))
      (node (ref "X6") (pin "2") (pinfunction "KL_2") (pintype "passive"))
    )
    (net (code "73") (name "Net-(U$14-M2)") (class "Default")
      (node (ref "R22") (pin "2") (pinfunction "2_2") (pintype "passive"))
      (node (ref "U$14") (pin "3") (pinfunction "M2_3") (pintype "bidirectional"))
      (node (ref "X7") (pin "1") (pinfunction "KL_1") (pintype "passive"))
    )
    (net (code "74") (name "VCC") (class "Default")
      (node (ref "IC1") (pin "10") (pinfunction "SCL_10") (pintype "input"))
      (node (ref "IC2") (pin "10") (pinfunction "SCL_10") (pintype "input"))
      (node (ref "JP1") (pin "1") (pinfunction "1_1") (pintype "passive"))
    )
    (net (code "75") (name "unconnected-(IC2A-QF-Pad5)") (class "Default")
      (node (ref "IC2") (pin "5") (pinfunction "QF_5") (pintype "tri_state"))
    )
    (net (code "76") (name "unconnected-(IC2A-QG-Pad6)") (class "Default")
      (node (ref "IC2") (pin "6") (pinfunction "QG_6") (pintype "tri_state"))
    )
    (net (code "77") (name "unconnected-(IC2A-QH*-Pad9)") (class "Default")
      (node (ref "IC2") (pin "9") (pinfunction "QH*_9") (pintype "tri_state"))
    )
    (net (code "78") (name "unconnected-(IC2A-QH-Pad7)") (class "Default")
      (node (ref "IC2") (pin "7") (pinfunction "QH_7") (pintype "tri_state"))
    )
  )
)
